# Decoupling_Caps.net
KiCad netlist of a schematic drawn in Altium Designer
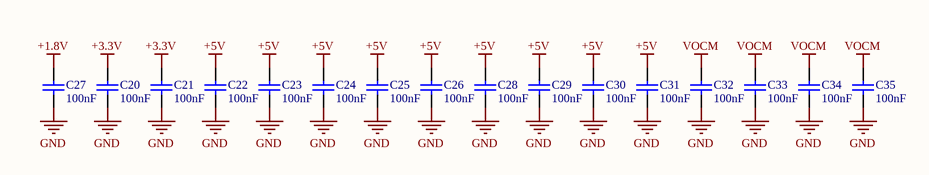
[diagram p0: Decoupling Caps.SchDoc]

(export (version "E")
  (design (tool "Eeschema 10.0.6"))
  (components
    (comp (ref "C20")
      (value "100nF")
      (footprint "CAPC0603(1608)55_M")
      (libsource (lib "Slivy's ibrary") (part "CAP"))
    )
    (comp (ref "C21")
      (value "100nF")
      (footprint "CAPC0603(1608)55_M")
      (libsource (lib "Slivy's ibrary") (part "CAP"))
    )
    (comp (ref "C22")
      (value "100nF")
      (footprint "CAPC0603(1608)55_M")
      (libsource (lib "Slivy's ibrary") (part "CAP"))
    )
    (comp (ref "C23")
      (value "100nF")
      (footprint "CAPC0603(1608)55_M")
      (libsource (lib "Slivy's ibrary") (part "CAP"))
    )
    (comp (ref "C24")
      (value "100nF")
      (footprint "CAPC0603(1608)55_M")
      (libsource (lib "Slivy's ibrary") (part "CAP"))
    )
    (comp (ref "C25")
      (value "100nF")
      (footprint "CAPC0603(1608)55_M")
      (libsource (lib "Slivy's ibrary") (part "CAP"))
    )
    (comp (ref "C26")
      (value "100nF")
      (footprint "CAPC0603(1608)55_M")
      (libsource (lib "Slivy's ibrary") (part "CAP"))
    )
    (comp (ref "C27")
      (value "100nF")
      (footprint "CAPC0603(1608)55_M")
      (libsource (lib "Slivy's ibrary") (part "CAP"))
    )
    (comp (ref "C28")
      (value "100nF")
      (footprint "CAPC0603(1608)55_M")
      (libsource (lib "Slivy's ibrary") (part "CAP"))
    )
    (comp (ref "C29")
      (value "100nF")
      (footprint "CAPC0603(1608)55_M")
      (libsource (lib "Slivy's ibrary") (part "CAP"))
    )
    (comp (ref "C30")
      (value "100nF")
      (footprint "CAPC0603(1608)55_M")
      (libsource (lib "Slivy's ibrary") (part "CAP"))
    )
    (comp (ref "C31")
      (value "100nF")
      (footprint "CAPC0603(1608)55_M")
      (libsource (lib "Slivy's ibrary") (part "CAP"))
    )
    (comp (ref "C32")
      (value "100nF")
      (footprint "CAPC0603(1608)55_M")
      (libsource (lib "Slivy's ibrary") (part "CAP"))
    )
    (comp (ref "C33")
      (value "100nF")
      (footprint "CAPC0603(1608)55_M")
      (libsource (lib "Slivy's ibrary") (part "CAP"))
    )
    (comp (ref "C34")
      (value "100nF")
      (footprint "CAPC0603(1608)55_M")
      (libsource (lib "Slivy's ibrary") (part "CAP"))
    )
    (comp (ref "C35")
      (value "100nF")
      (footprint "CAPC0603(1608)55_M")
      (libsource (lib "Slivy's ibrary") (part "CAP"))
    )
  )
  (nets
    (net (code "1") (name "+1.8V") (class "Default")
      (node (ref "C27") (pin "2") (pinfunction "2_2") (pintype "passive"))
    )
    (net (code "2") (name "+3.3V") (class "Default")
      (node (ref "C20") (pin "2") (pinfunction "2_2") (pintype "passive"))
      (node (ref "C21") (pin "2") (pinfunction "2_2") (pintype "passive"))
    )
    (net (code "3") (name "+5V") (class "Default")
      (node (ref "C22") (pin "2") (pinfunction "2_2") (pintype "passive"))
      (node (ref "C23") (pin "2") (pinfunction "2_2") (pintype "passive"))
      (node (ref "C24") (pin "2") (pinfunction "2_2") (pintype "passive"))
      (node (ref "C25") (pin "2") (pinfunction "2_2") (pintype "passive"))
      (node (ref "C26") (pin "2") (pinfunction "2_2") (pintype "passive"))
      (node (ref "C28") (pin "2") (pinfunction "2_2") (pintype "passive"))
      (node (ref "C29") (pin "2") (pinfunction "2_2") (pintype "passive"))
      (node (ref "C30") (pin "2") (pinfunction "2_2") (pintype "passive"))
      (node (ref "C31") (pin "2") (pinfunction "2_2") (pintype "passive"))
    )
    (net (code "4") (name "GND") (class "Default")
      (node (ref "C20") (pin "1") (pinfunction "1_1") (pintype "passive"))
      (node (ref "C21") (pin "1") (pinfunction "1_1") (pintype "passive"))
      (node (ref "C22") (pin "1") (pinfunction "1_1") (pintype "passive"))
      (node (ref "C23") (pin "1") (pinfunction "1_1") (pintype "passive"))
      (node (ref "C24") (pin "1") (pinfunction "1_1") (pintype "passive"))
      (node (ref "C25") (pin "1") (pinfunction "1_1") (pintype "passive"))
      (node (ref "C26") (pin "1") (pinfunction "1_1") (pintype "passive"))
      (node (ref "C27") (pin "1") (pinfunction "1_1") (pintype "passive"))
      (node (ref "C28") (pin "1") (pinfunction "1_1") (pintype "passive"))
      (node (ref "C29") (pin "1") (pinfunction "1_1") (pintype "passive"))
      (node (ref "C30") (pin "1") (pinfunction "1_1") (pintype "passive"))
      (node (ref "C31") (pin "1") (pinfunction "1_1") (pintype "passive"))
      (node (ref "C32") (pin "1") (pinfunction "1_1") (pintype "passive"))
      (node (ref "C33") (pin "1") (pinfunction "1_1") (pintype "passive"))
      (node (ref "C34") (pin "1") (pinfunction "1_1") (pintype "passive"))
      (node (ref "C35") (pin "1") (pinfunction "1_1") (pintype "passive"))
    )
    (net (code "5") (name "VOCM") (class "Default")
      (node (ref "C32") (pin "2") (pinfunction "2_2") (pintype "passive"))
      (node (ref "C33") (pin "2") (pinfunction "2_2") (pintype "passive"))
      (node (ref "C34") (pin "2") (pinfunction "2_2") (pintype "passive"))
      (node (ref "C35") (pin "2") (pinfunction "2_2") (pintype "passive"))
    )
  )
)
